# pic12f509-rgb-pwm.net
KiCad netlist of a schematic drawn in EAGLE
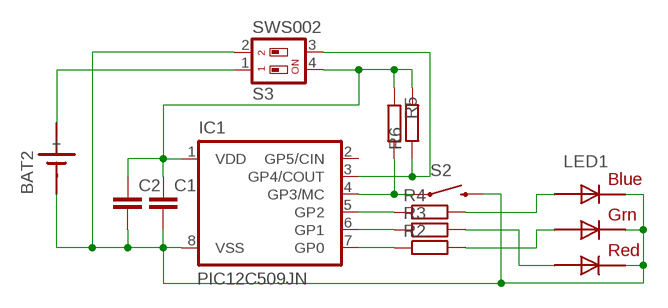
[diagram p0: schematic, sheet 1]

(export (version "E")
  (design (tool "Eeschema 10.0.6"))
  (components
    (comp (ref "BAT2")
      (value "SN2032")
      (footprint "eagle-import:SN2032")
      (libsource (lib "eagle-import") (part "SN2032"))
    )
    (comp (ref "C1")
      (value "C-EUC0805K")
      (footprint "eagle-import:C0805K")
      (libsource (lib "eagle-import") (part "C-EUC0805K"))
    )
    (comp (ref "C2")
      (value "C-EUC0805K")
      (footprint "eagle-import:C0805K")
      (libsource (lib "eagle-import") (part "C-EUC0805K"))
    )
    (comp (ref "IC1")
      (value "PIC12C509JN")
      (footprint "eagle-import:DIL8")
      (fields (field (name "MF") "MICROCHIP") (field (name "MPN") "PIC12C509A-04I/P"))
      (libsource (lib "eagle-import") (part "PIC12C?JN509"))
    )
    (comp (ref "LED1")
      (value "RGBLED5050")
      (footprint "eagle-import:RGBLED5050")
      (libsource (lib "eagle-import") (part "RGBLED5050"))
    )
    (comp (ref "R2")
      (value "R-EU_M0805")
      (footprint "eagle-import:M0805")
      (libsource (lib "eagle-import") (part "R-EU_M0805"))
    )
    (comp (ref "R3")
      (value "R-EU_M0805")
      (footprint "eagle-import:M0805")
      (libsource (lib "eagle-import") (part "R-EU_M0805"))
    )
    (comp (ref "R4")
      (value "R-EU_M0805")
      (footprint "eagle-import:M0805")
      (libsource (lib "eagle-import") (part "R-EU_M0805"))
    )
    (comp (ref "R5")
      (value "R-EU_M0805")
      (footprint "eagle-import:M0805")
      (libsource (lib "eagle-import") (part "R-EU_M0805"))
    )
    (comp (ref "R6")
      (value "R-EU_M0805")
      (footprint "eagle-import:M0805")
      (libsource (lib "eagle-import") (part "R-EU_M0805"))
    )
    (comp (ref "S2")
      (value "SWITCH-MOMENTARY-2-SMD-1101NE")
      (footprint "eagle-import:TACTILE-SWITCH-1101NE")
      (libsource (lib "eagle-import") (part "SWITCH-MOMENTARY-2-SMD-1101NE"))
    )
    (comp (ref "S3")
      (value "SWS002")
      (footprint "eagle-import:SMS-002")
      (libsource (lib "eagle-import") (part "SWS002"))
    )
  )
  (nets
    (net (code "1") (name "Net-(BAT2-Pad+)") (class "Default")
      (node (ref "BAT2") (pin "+") (pinfunction "+_+") (pintype "passive"))
      (node (ref "S3") (pin "1") (pinfunction "1_1") (pintype "passive"))
    )
    (net (code "2") (name "Net-(IC1-GP0)") (class "Default")
      (node (ref "IC1") (pin "7") (pinfunction "GP0_7") (pintype "bidirectional"))
      (node (ref "R2") (pin "1") (pinfunction "1_1") (pintype "passive"))
    )
    (net (code "3") (name "Net-(IC1-GP1)") (class "Default")
      (node (ref "IC1") (pin "6") (pinfunction "GP1_6") (pintype "bidirectional"))
      (node (ref "R3") (pin "1") (pinfunction "1_1") (pintype "passive"))
    )
    (net (code "4") (name "Net-(IC1-GP2)") (class "Default")
      (node (ref "IC1") (pin "5") (pinfunction "GP2_5") (pintype "bidirectional"))
      (node (ref "R4") (pin "1") (pinfunction "1_1") (pintype "passive"))
    )
    (net (code "5") (name "Net-(IC1-GP3{slash}MC)") (class "Default")
      (node (ref "IC1") (pin "4") (pinfunction "GP3/MC_4") (pintype "input"))
      (node (ref "R5") (pin "2") (pinfunction "2_2") (pintype "passive"))
      (node (ref "S2") (pin "1") (pinfunction "1_1") (pintype "passive"))
    )
    (net (code "6") (name "Net-(IC1-GP4{slash}COUT)") (class "Default")
      (node (ref "IC1") (pin "3") (pinfunction "GP4/COUT_3") (pintype "bidirectional"))
      (node (ref "R6") (pin "1") (pinfunction "1_1") (pintype "passive"))
      (node (ref "S3") (pin "3") (pinfunction "3_3") (pintype "passive"))
    )
    (net (code "7") (name "Net-(IC1-VDD)") (class "Default")
      (node (ref "C1") (pin "1") (pinfunction "1_1") (pintype "passive"))
      (node (ref "C2") (pin "1") (pinfunction "1_1") (pintype "passive"))
      (node (ref "IC1") (pin "1") (pinfunction "VDD_1") (pintype "power_in"))
      (node (ref "R5") (pin "1") (pinfunction "1_1") (pintype "passive"))
      (node (ref "R6") (pin "2") (pinfunction "2_2") (pintype "passive"))
      (node (ref "S3") (pin "4") (pinfunction "4_4") (pintype "passive"))
    )
    (net (code "8") (name "Net-(IC1-VSS)") (class "Default")
      (node (ref "BAT2") (pin "-") (pinfunction "-_-") (pintype "passive"))
      (node (ref "C1") (pin "2") (pinfunction "2_2") (pintype "passive"))
      (node (ref "C2") (pin "2") (pinfunction "2_2") (pintype "passive"))
      (node (ref "IC1") (pin "8") (pinfunction "VSS_8") (pintype "power_in"))
      (node (ref "LED1") (pin "4") (pinfunction "BLUE_C_4") (pintype "bidirectional"))
      (node (ref "LED1") (pin "5") (pinfunction "RED_C_5") (pintype "bidirectional"))
      (node (ref "LED1") (pin "6") (pinfunction "GREEN_C_6") (pintype "bidirectional"))
      (node (ref "S2") (pin "2") (pinfunction "2_2") (pintype "passive"))
      (node (ref "S3") (pin "2") (pinfunction "2_2") (pintype "passive"))
    )
    (net (code "9") (name "Net-(LED1-BLUE_A)") (class "Default")
      (node (ref "LED1") (pin "3") (pinfunction "BLUE_A_3") (pintype "bidirectional"))
      (node (ref "R4") (pin "2") (pinfunction "2_2") (pintype "passive"))
    )
    (net (code "10") (name "Net-(LED1-GREEN_A)") (class "Default")
      (node (ref "LED1") (pin "1") (pinfunction "GREEN_A_1") (pintype "bidirectional"))
      (node (ref "R2") (pin "2") (pinfunction "2_2") (pintype "passive"))
    )
    (net (code "11") (name "Net-(LED1-RED_A)") (class "Default")
      (node (ref "LED1") (pin "2") (pinfunction "RED_A_2") (pintype "bidirectional"))
      (node (ref "R3") (pin "2") (pinfunction "2_2") (pintype "passive"))
    )
    (net (code "12") (name "unconnected-(IC1-GP5{slash}CIN-Pad2)") (class "Default")
      (node (ref "IC1") (pin "2") (pinfunction "GP5/CIN_2") (pintype "bidirectional"))
    )
  )
)
